# STM32F401.net
KiCad netlist of a schematic drawn in Altium Designer
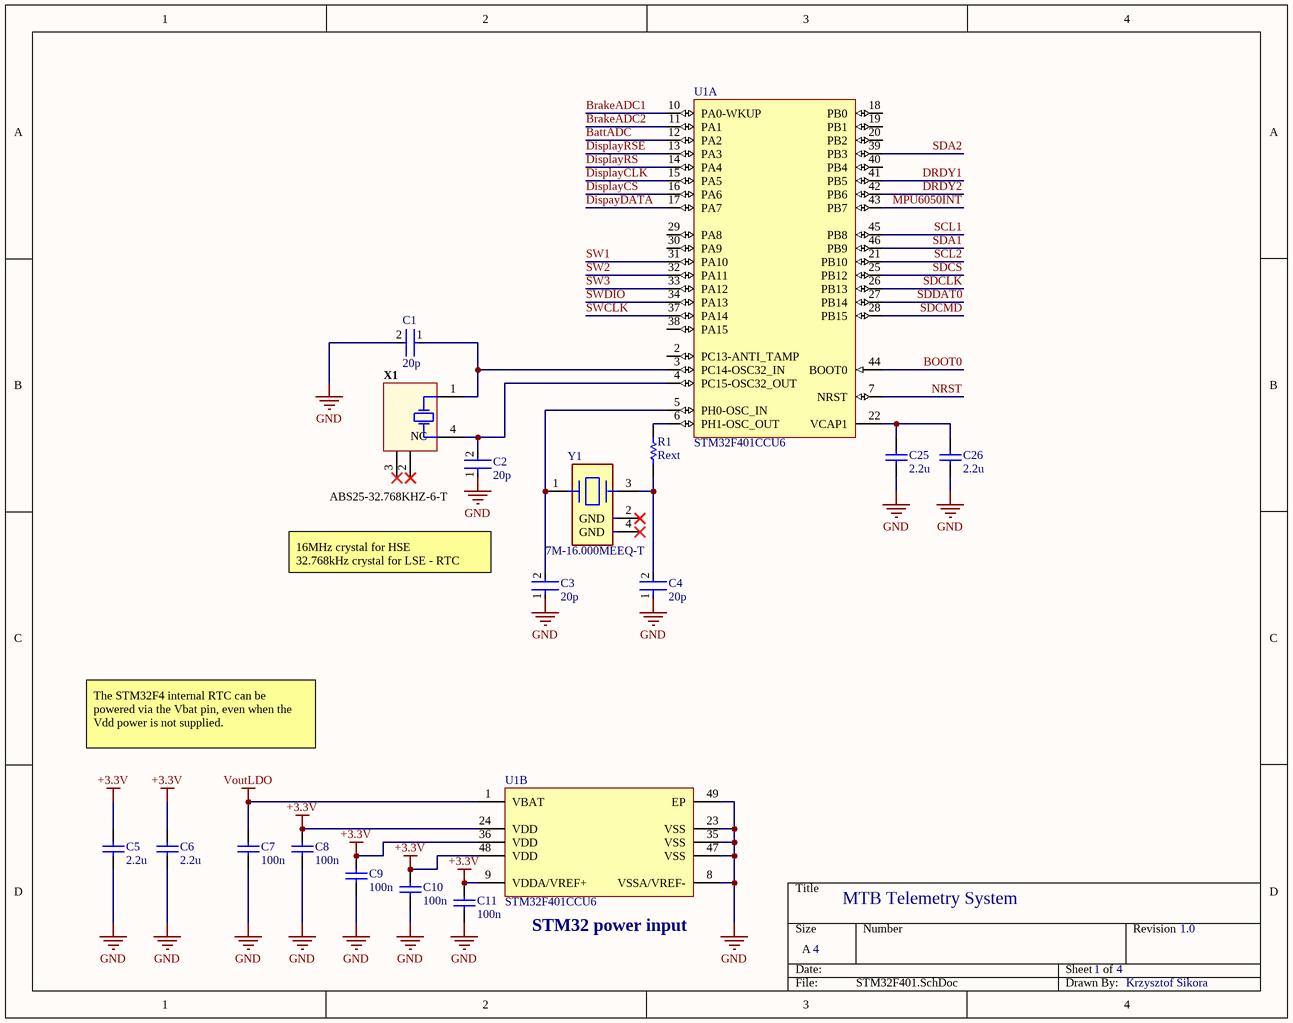
[diagram p0: STM32F401.SchDoc]

(export (version "E")
  (design (tool "Eeschema 10.0.6"))
  (components
    (comp (ref "C1")
      (value "20p")
      (footprint "FP-C0603C-CF-MFG")
      (description "CAP CER 0.1UF 50V X7R 0603")
      (fields (field (name "TOLERANCE") "0.1") (field (name "MANUFACTURER") "KEMET"))
      (libsource (lib "Altium Content Vault") (part "b4654b650e69147ec39a6b967a45e02"))
    )
    (comp (ref "C2")
      (value "20p")
      (footprint "FP-C0603C-CF-MFG")
      (description "CAP CER 0.1UF 50V X7R 0603")
      (fields (field (name "TOLERANCE") "0.1") (field (name "MANUFACTURER") "KEMET"))
      (libsource (lib "Altium Content Vault") (part "b4654b650e69147ec39a6b967a45e02"))
    )
    (comp (ref "C3")
      (value "20p")
      (footprint "FP-C0603C-CF-MFG")
      (description "CAP CER 0.1UF 50V X7R 0603")
      (fields (field (name "TOLERANCE") "0.1") (field (name "MANUFACTURER") "KEMET"))
      (libsource (lib "Altium Content Vault") (part "b4654b650e69147ec39a6b967a45e02"))
    )
    (comp (ref "C4")
      (value "20p")
      (footprint "FP-C0603C-CF-MFG")
      (description "CAP CER 0.1UF 50V X7R 0603")
      (fields (field (name "TOLERANCE") "0.1") (field (name "MANUFACTURER") "KEMET"))
      (libsource (lib "Altium Content Vault") (part "b4654b650e69147ec39a6b967a45e02"))
    )
    (comp (ref "C5")
      (value "2.2u")
      (footprint "CAPC2013X88X50LL20T25")
      (fields (field (name "MANUFACTURER") "Kemet") (field (name "PART NUMBER") "C0805C103K5RACTU"))
      (libsource (lib "Altium Content Vault") (part "CAP"))
    )
    (comp (ref "C6")
      (value "2.2u")
      (footprint "CAPC2013X88X50LL20T25")
      (fields (field (name "MANUFACTURER") "Kemet") (field (name "PART NUMBER") "C0805C103K5RACTU"))
      (libsource (lib "Altium Content Vault") (part "CAP"))
    )
    (comp (ref "C7")
      (value "100n")
      (footprint "CAPC2013X88X50LL20T25")
      (fields (field (name "MANUFACTURER") "Kemet") (field (name "PART NUMBER") "C0805C103K5RACTU"))
      (libsource (lib "Altium Content Vault") (part "CAP"))
    )
    (comp (ref "C8")
      (value "100n")
      (footprint "CAPC2013X88X50LL20T25")
      (fields (field (name "MANUFACTURER") "Kemet") (field (name "PART NUMBER") "C0805C103K5RACTU"))
      (libsource (lib "Altium Content Vault") (part "CAP"))
    )
    (comp (ref "C9")
      (value "100n")
      (footprint "CAPC2013X88X50LL20T25")
      (fields (field (name "MANUFACTURER") "Kemet") (field (name "PART NUMBER") "C0805C103K5RACTU"))
      (libsource (lib "Altium Content Vault") (part "CAP"))
    )
    (comp (ref "C10")
      (value "100n")
      (footprint "CAPC2013X88X50LL20T25")
      (fields (field (name "MANUFACTURER") "Kemet") (field (name "PART NUMBER") "C0805C103K5RACTU"))
      (libsource (lib "Altium Content Vault") (part "CAP"))
    )
    (comp (ref "C11")
      (value "100n")
      (footprint "CAPC2013X88X50LL20T25")
      (fields (field (name "MANUFACTURER") "Kemet") (field (name "PART NUMBER") "C0805C103K5RACTU"))
      (libsource (lib "Altium Content Vault") (part "CAP"))
    )
    (comp (ref "C25")
      (value "2.2u")
      (footprint "CAPC2013X88X50LL20T25")
      (fields (field (name "MANUFACTURER") "Kemet") (field (name "PART NUMBER") "C0805C103K5RACTU"))
      (libsource (lib "Altium Content Vault") (part "CAP"))
    )
    (comp (ref "C26")
      (value "2.2u")
      (footprint "CAPC2013X88X50LL20T25")
      (fields (field (name "MANUFACTURER") "Kemet") (field (name "PART NUMBER") "C0805C103K5RACTU"))
      (libsource (lib "Altium Content Vault") (part "CAP"))
    )
    (comp (ref "R1")
      (value "Rext")
      (footprint "RESC1609X50X30NL8T20")
      (description "Chip Resistor, 10 KOhm, +/- 1%, 100 mW, -55 to 155 degC, 0603 (1608 Metric), RoHS, Tape and Reel")
      (fields (field (name "MANUFACTURER") "Vishay Semiconductor"))
      (libsource (lib "Altium Content Vault") (part "RES-2"))
    )
    (comp (ref "U1")
      (value "STM32F401CCU6")
      (footprint "STM-UFQFPN48_N")
      (fields (field (name "MANUFACTURER") "STMicroelectronics"))
      (libsource (lib "Altium Content Vault") (part "MC-ARM-STM32F401-SQ48"))
    )
    (comp (ref "X1")
      (value "ABS25-32.768KHZ-6-T")
      (footprint "ABRA-ABS25-4_V")
      (fields (field (name "TOLERANCE") "20PPM") (field (name "MANUFACTURER") "Abracon"))
      (libsource (lib "Altium Content Vault") (part "ABRA-XTAL_1-4-4"))
    )
    (comp (ref "Y1")
      (value "7M-16.000MEEQ-T")
      (footprint "FP-7M-MFG")
      (description "Crystal 16MHz, 10ppm, 10pF, 60Ω")
      (fields (field (name "TOLERANCE") "10ppm"))
      (libsource (lib "Altium Content Vault") (part "41079aabb0e87794b56622915be14ed"))
    )
  )
  (nets
    (net (code "1") (name "+3.3V") (class "Default")
      (node (ref "C10") (pin "2") (pinfunction "2_2") (pintype "passive"))
      (node (ref "C11") (pin "2") (pinfunction "2_2") (pintype "passive"))
      (node (ref "C5") (pin "2") (pinfunction "2_2") (pintype "passive"))
      (node (ref "C6") (pin "2") (pinfunction "2_2") (pintype "passive"))
      (node (ref "C8") (pin "2") (pinfunction "2_2") (pintype "passive"))
      (node (ref "C9") (pin "2") (pinfunction "2_2") (pintype "passive"))
      (node (ref "U1") (pin "24") (pinfunction "VDD_24") (pintype "power_in"))
      (node (ref "U1") (pin "36") (pinfunction "VDD_36") (pintype "power_in"))
      (node (ref "U1") (pin "48") (pinfunction "VDD_48") (pintype "power_in"))
      (node (ref "U1") (pin "9") (pinfunction "VDDA/VREF+_9") (pintype "power_in"))
    )
    (net (code "2") (name "/BOOT0") (class "Default")
      (node (ref "U1") (pin "44") (pinfunction "BOOT0_44") (pintype "input"))
    )
    (net (code "3") (name "/BattADC") (class "Default")
      (node (ref "U1") (pin "12") (pinfunction "PA2_12") (pintype "bidirectional"))
    )
    (net (code "4") (name "/BrakeADC1") (class "Default")
      (node (ref "U1") (pin "10") (pinfunction "PA0-WKUP_10") (pintype "bidirectional"))
    )
    (net (code "5") (name "/BrakeADC2") (class "Default")
      (node (ref "U1") (pin "11") (pinfunction "PA1_11") (pintype "bidirectional"))
    )
    (net (code "6") (name "/DRDY1") (class "Default")
      (node (ref "U1") (pin "41") (pinfunction "PB5_41") (pintype "bidirectional"))
    )
    (net (code "7") (name "/DRDY2") (class "Default")
      (node (ref "U1") (pin "42") (pinfunction "PB6_42") (pintype "bidirectional"))
    )
    (net (code "8") (name "/DispayDATA") (class "Default")
      (node (ref "U1") (pin "17") (pinfunction "PA7_17") (pintype "bidirectional"))
    )
    (net (code "9") (name "/DisplayCLK") (class "Default")
      (node (ref "U1") (pin "15") (pinfunction "PA5_15") (pintype "bidirectional"))
    )
    (net (code "10") (name "/DisplayCS") (class "Default")
      (node (ref "U1") (pin "16") (pinfunction "PA6_16") (pintype "bidirectional"))
    )
    (net (code "11") (name "/DisplayRS") (class "Default")
      (node (ref "U1") (pin "14") (pinfunction "PA4_14") (pintype "bidirectional"))
    )
    (net (code "12") (name "/DisplayRSE") (class "Default")
      (node (ref "U1") (pin "13") (pinfunction "PA3_13") (pintype "bidirectional"))
    )
    (net (code "13") (name "/MPU6050INT") (class "Default")
      (node (ref "U1") (pin "43") (pinfunction "PB7_43") (pintype "bidirectional"))
    )
    (net (code "14") (name "/NRST") (class "Default")
      (node (ref "U1") (pin "7") (pinfunction "NRST_7") (pintype "bidirectional"))
    )
    (net (code "15") (name "/SCL1") (class "Default")
      (node (ref "U1") (pin "45") (pinfunction "PB8_45") (pintype "bidirectional"))
    )
    (net (code "16") (name "/SCL2") (class "Default")
      (node (ref "U1") (pin "21") (pinfunction "PB10_21") (pintype "bidirectional"))
    )
    (net (code "17") (name "/SDA1") (class "Default")
      (node (ref "U1") (pin "46") (pinfunction "PB9_46") (pintype "bidirectional"))
    )
    (net (code "18") (name "/SDA2") (class "Default")
      (node (ref "U1") (pin "39") (pinfunction "PB3_39") (pintype "bidirectional"))
    )
    (net (code "19") (name "/SDCLK") (class "Default")
      (node (ref "U1") (pin "26") (pinfunction "PB13_26") (pintype "bidirectional"))
    )
    (net (code "20") (name "/SDCMD") (class "Default")
      (node (ref "U1") (pin "28") (pinfunction "PB15_28") (pintype "bidirectional"))
    )
    (net (code "21") (name "/SDCS") (class "Default")
      (node (ref "U1") (pin "25") (pinfunction "PB12_25") (pintype "bidirectional"))
    )
    (net (code "22") (name "/SDDAT0") (class "Default")
      (node (ref "U1") (pin "27") (pinfunction "PB14_27") (pintype "bidirectional"))
    )
    (net (code "23") (name "/SW1") (class "Default")
      (node (ref "U1") (pin "31") (pinfunction "PA10_31") (pintype "bidirectional"))
    )
    (net (code "24") (name "/SW2") (class "Default")
      (node (ref "U1") (pin "32") (pinfunction "PA11_32") (pintype "bidirectional"))
    )
    (net (code "25") (name "/SW3") (class "Default")
      (node (ref "U1") (pin "33") (pinfunction "PA12_33") (pintype "bidirectional"))
    )
    (net (code "26") (name "/SWCLK") (class "Default")
      (node (ref "U1") (pin "37") (pinfunction "PA14_37") (pintype "bidirectional"))
    )
    (net (code "27") (name "/SWDIO") (class "Default")
      (node (ref "U1") (pin "34") (pinfunction "PA13_34") (pintype "bidirectional"))
    )
    (net (code "28") (name "GND") (class "Default")
      (node (ref "C1") (pin "2") (pinfunction "2_2") (pintype "passive"))
      (node (ref "C10") (pin "1") (pinfunction "1_1") (pintype "passive"))
      (node (ref "C11") (pin "1") (pinfunction "1_1") (pintype "passive"))
      (node (ref "C2") (pin "1") (pinfunction "1_1") (pintype "passive"))
      (node (ref "C25") (pin "1") (pinfunction "1_1") (pintype "passive"))
      (node (ref "C26") (pin "1") (pinfunction "1_1") (pintype "passive"))
      (node (ref "C3") (pin "1") (pinfunction "1_1") (pintype "passive"))
      (node (ref "C4") (pin "1") (pinfunction "1_1") (pintype "passive"))
      (node (ref "C5") (pin "1") (pinfunction "1_1") (pintype "passive"))
      (node (ref "C6") (pin "1") (pinfunction "1_1") (pintype "passive"))
      (node (ref "C7") (pin "1") (pinfunction "1_1") (pintype "passive"))
      (node (ref "C8") (pin "1") (pinfunction "1_1") (pintype "passive"))
      (node (ref "C9") (pin "1") (pinfunction "1_1") (pintype "passive"))
      (node (ref "U1") (pin "23") (pinfunction "VSS_23") (pintype "power_in"))
      (node (ref "U1") (pin "35") (pinfunction "VSS_35") (pintype "power_in"))
      (node (ref "U1") (pin "47") (pinfunction "VSS_47") (pintype "power_in"))
      (node (ref "U1") (pin "49") (pinfunction "EP_49") (pintype "power_in"))
      (node (ref "U1") (pin "8") (pinfunction "VSSA/VREF-_8") (pintype "power_in"))
    )
    (net (code "29") (name "Net-(C4-Pad2)") (class "Default")
      (node (ref "C4") (pin "2") (pinfunction "2_2") (pintype "passive"))
      (node (ref "R1") (pin "1") (pinfunction "1_1") (pintype "passive"))
      (node (ref "Y1") (pin "3") (pinfunction "3_3") (pintype "passive"))
    )
    (net (code "30") (name "Net-(U1A-PC14-OSC32_IN)") (class "Default")
      (node (ref "C1") (pin "1") (pinfunction "1_1") (pintype "passive"))
      (node (ref "U1") (pin "3") (pinfunction "PC14-OSC32_IN_3") (pintype "bidirectional"))
      (node (ref "X1") (pin "1") (pinfunction "X1_1") (pintype "passive"))
    )
    (net (code "31") (name "Net-(U1A-PC15-OSC32_OUT)") (class "Default")
      (node (ref "C2") (pin "2") (pinfunction "2_2") (pintype "passive"))
      (node (ref "U1") (pin "4") (pinfunction "PC15-OSC32_OUT_4") (pintype "bidirectional"))
      (node (ref "X1") (pin "4") (pinfunction "X2_4") (pintype "passive"))
    )
    (net (code "32") (name "Net-(U1A-PH0-OSC_IN)") (class "Default")
      (node (ref "C3") (pin "2") (pinfunction "2_2") (pintype "passive"))
      (node (ref "U1") (pin "5") (pinfunction "PH0-OSC_IN_5") (pintype "bidirectional"))
      (node (ref "Y1") (pin "1") (pinfunction "1_1") (pintype "passive"))
    )
    (net (code "33") (name "Net-(U1A-PH1-OSC_OUT)") (class "Default")
      (node (ref "R1") (pin "2") (pinfunction "2_2") (pintype "passive"))
      (node (ref "U1") (pin "6") (pinfunction "PH1-OSC_OUT_6") (pintype "bidirectional"))
    )
    (net (code "34") (name "Net-(U1A-VCAP1)") (class "Default")
      (node (ref "C25") (pin "2") (pinfunction "2_2") (pintype "passive"))
      (node (ref "C26") (pin "2") (pinfunction "2_2") (pintype "passive"))
      (node (ref "U1") (pin "22") (pinfunction "VCAP1_22") (pintype "power_in"))
    )
    (net (code "35") (name "VoutLDO") (class "Default")
      (node (ref "C7") (pin "2") (pinfunction "2_2") (pintype "passive"))
      (node (ref "U1") (pin "1") (pinfunction "VBAT_1") (pintype "power_in"))
    )
    (net (code "36") (name "unconnected-(U1A-PA8-Pad29)") (class "Default")
      (node (ref "U1") (pin "29") (pinfunction "PA8_29") (pintype "bidirectional"))
    )
    (net (code "37") (name "unconnected-(U1A-PA9-Pad30)") (class "Default")
      (node (ref "U1") (pin "30") (pinfunction "PA9_30") (pintype "bidirectional"))
    )
    (net (code "38") (name "unconnected-(U1A-PA15-Pad38)") (class "Default")
      (node (ref "U1") (pin "38") (pinfunction "PA15_38") (pintype "bidirectional"))
    )
    (net (code "39") (name "unconnected-(U1A-PB0-Pad18)") (class "Default")
      (node (ref "U1") (pin "18") (pinfunction "PB0_18") (pintype "bidirectional"))
    )
    (net (code "40") (name "unconnected-(U1A-PB1-Pad19)") (class "Default")
      (node (ref "U1") (pin "19") (pinfunction "PB1_19") (pintype "bidirectional"))
    )
    (net (code "41") (name "unconnected-(U1A-PB2-Pad20)") (class "Default")
      (node (ref "U1") (pin "20") (pinfunction "PB2_20") (pintype "bidirectional"))
    )
    (net (code "42") (name "unconnected-(U1A-PB4-Pad40)") (class "Default")
      (node (ref "U1") (pin "40") (pinfunction "PB4_40") (pintype "bidirectional"))
    )
    (net (code "43") (name "unconnected-(U1A-PC13-ANTI_TAMP-Pad2)") (class "Default")
      (node (ref "U1") (pin "2") (pinfunction "PC13-ANTI_TAMP_2") (pintype "bidirectional"))
    )
    (net (code "44") (name "unconnected-(X1-NC-Pad2)") (class "Default")
      (node (ref "X1") (pin "2") (pinfunction "NC_2") (pintype "passive+no_connect"))
    )
    (net (code "45") (name "unconnected-(X1-NC-Pad3)") (class "Default")
      (node (ref "X1") (pin "3") (pinfunction "NC_3") (pintype "passive+no_connect"))
    )
    (net (code "46") (name "unconnected-(Y1-GND-Pad2)") (class "Default")
      (node (ref "Y1") (pin "2") (pinfunction "GND_2") (pintype "power_in+no_connect"))
    )
    (net (code "47") (name "unconnected-(Y1-GND-Pad4)") (class "Default")
      (node (ref "Y1") (pin "4") (pinfunction "GND_4") (pintype "power_in+no_connect"))
    )
  )
)
